# untitled.net
KiCad netlist of a schematic drawn in EAGLE
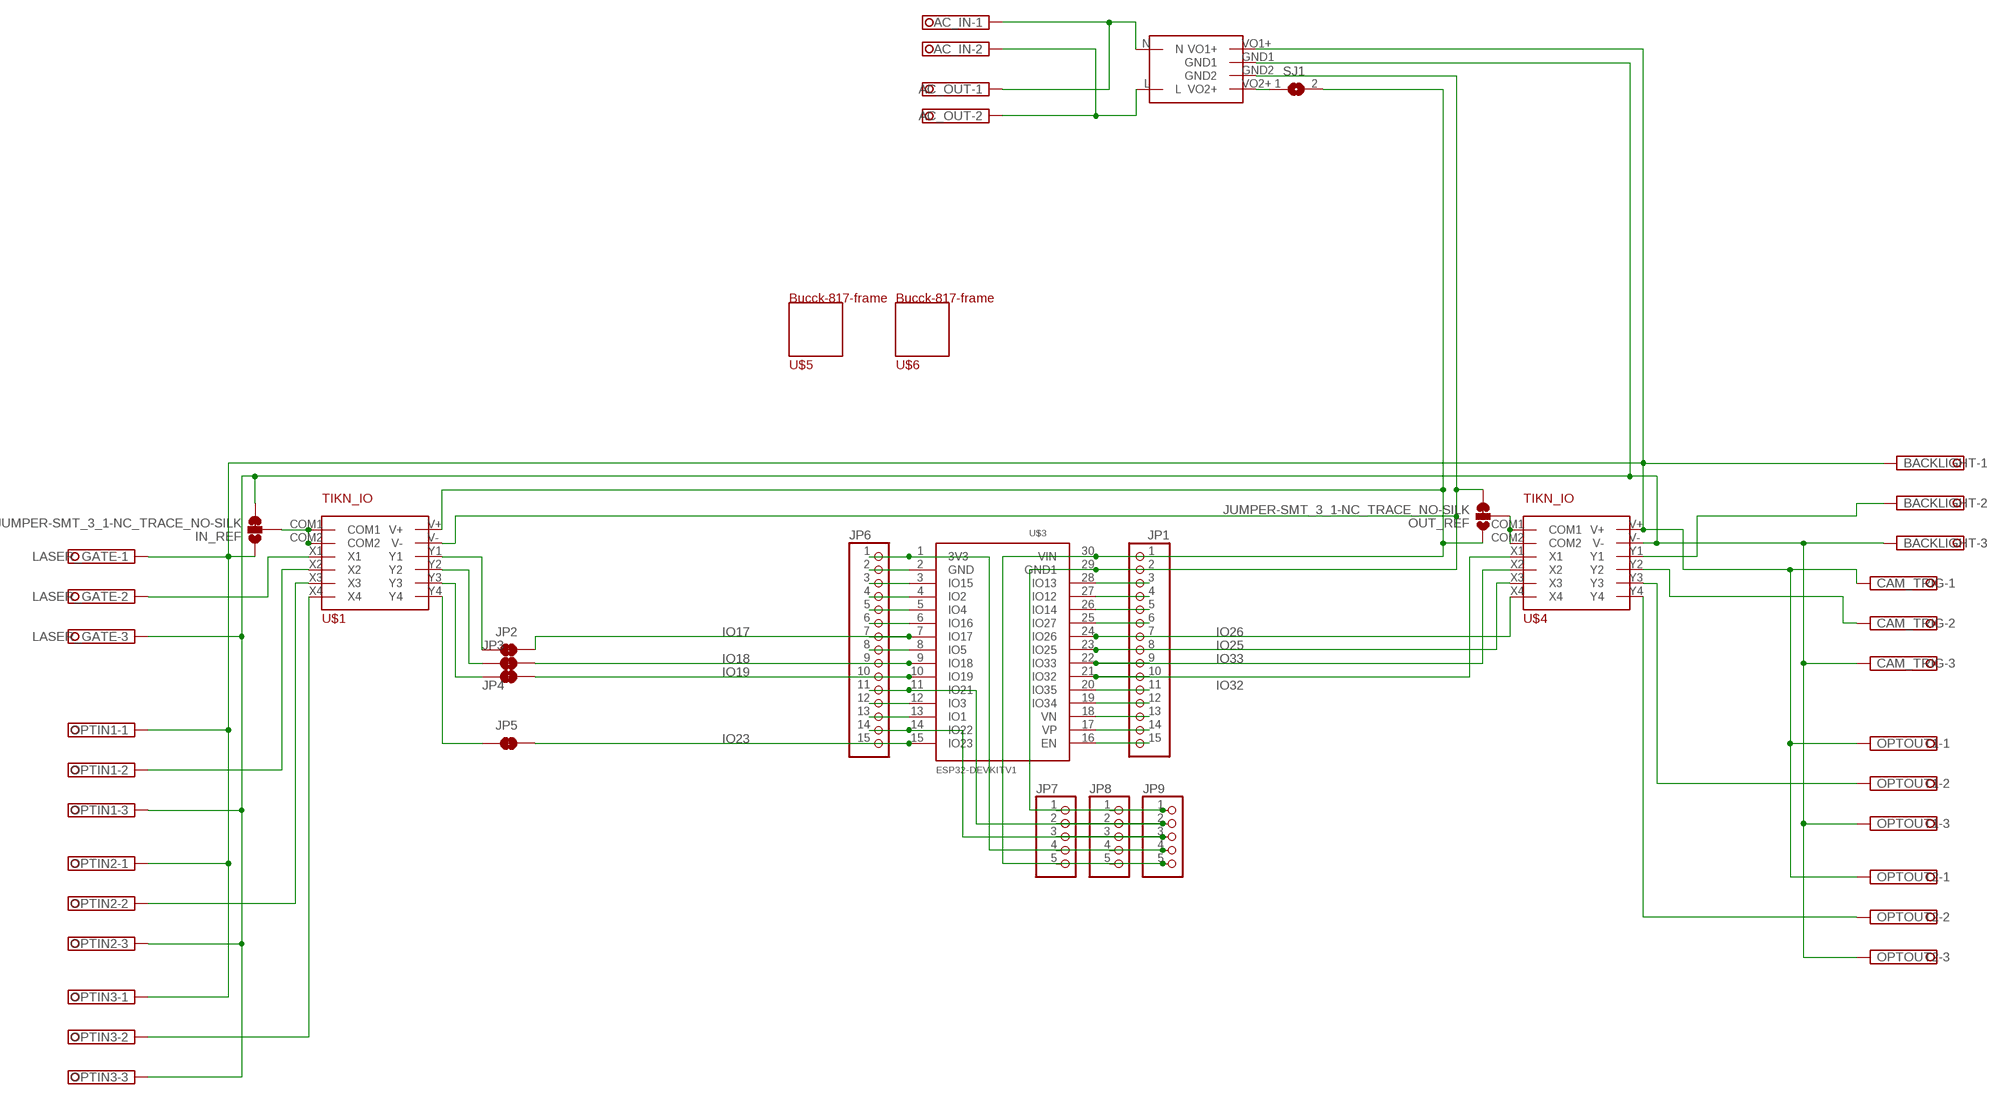
[diagram p0: schematic, sheet 1]

(export (version "E")
  (design (tool "Eeschema 10.0.6"))
  (components
    (comp (ref "AC_IN")
      (value "TERMINAL-BLOCK-3.5MM-2-PIN-LONG-PAD")
      (footprint "eagle-import:TERMINAL-BLOCK-2-PIN-3.5MM-LONG-PAD")
      (libsource (lib "eagle-import") (part "TERMINAL-BLOCK-3.5MM-2-PIN-LONG-PAD"))
    )
    (comp (ref "AC_OUT")
      (value "TERMINAL-BLOCK-3.5MM-2-PIN-LONG-PAD")
      (footprint "eagle-import:TERMINAL-BLOCK-2-PIN-3.5MM-LONG-PAD")
      (libsource (lib "eagle-import") (part "TERMINAL-BLOCK-3.5MM-2-PIN-LONG-PAD"))
    )
    (comp (ref "BACKLIGHT")
      (value "TERMINAL-BLOCK-3.5MM-3-PIN-LONG-PAD")
      (footprint "eagle-import:TERMINAL-BLOCK-3-PIN-3.5MM-LONG-PAD")
      (libsource (lib "eagle-import") (part "TERMINAL-BLOCK-3.5MM-3-PIN-LONG-PAD"))
    )
    (comp (ref "CAM_TRIG")
      (value "TERMINAL-BLOCK-3.5MM-3-PIN-LONG-PAD")
      (footprint "eagle-import:TERMINAL-BLOCK-3-PIN-3.5MM-LONG-PAD")
      (libsource (lib "eagle-import") (part "TERMINAL-BLOCK-3.5MM-3-PIN-LONG-PAD"))
    )
    (comp (ref "IN_REF")
      (value "JUMPER-SMT_3_1-NC_TRACE_NO-SILK")
      (footprint "eagle-import:SMT-JUMPER_3_1-NC_TRACE_NO-SILK")
      (libsource (lib "eagle-import") (part "JUMPER-SMT_3_1-NC_TRACE_NO-SILK"))
    )
    (comp (ref "JP1")
      (value "PINHD-1X15")
      (footprint "eagle-import:1X15")
      (libsource (lib "eagle-import") (part "PINHD-1X15"))
    )
    (comp (ref "JP2")
      (value "JUMPER-SMT_2_NC_TRACE_SILK")
      (footprint "eagle-import:SMT-JUMPER_2_NC_TRACE_SILK")
      (libsource (lib "eagle-import") (part "JUMPER-SMT_2_NC_TRACE_SILK"))
    )
    (comp (ref "JP3")
      (value "JUMPER-SMT_2_NC_TRACE_SILK")
      (footprint "eagle-import:SMT-JUMPER_2_NC_TRACE_SILK")
      (libsource (lib "eagle-import") (part "JUMPER-SMT_2_NC_TRACE_SILK"))
    )
    (comp (ref "JP4")
      (value "JUMPER-SMT_2_NC_TRACE_SILK")
      (footprint "eagle-import:SMT-JUMPER_2_NC_TRACE_SILK")
      (libsource (lib "eagle-import") (part "JUMPER-SMT_2_NC_TRACE_SILK"))
    )
    (comp (ref "JP5")
      (value "JUMPER-SMT_2_NC_TRACE_SILK")
      (footprint "eagle-import:SMT-JUMPER_2_NC_TRACE_SILK")
      (libsource (lib "eagle-import") (part "JUMPER-SMT_2_NC_TRACE_SILK"))
    )
    (comp (ref "JP6")
      (value "PINHD-1X15")
      (footprint "eagle-import:1X15")
      (libsource (lib "eagle-import") (part "PINHD-1X15"))
    )
    (comp (ref "JP7")
      (value "PINHD-1X5")
      (footprint "eagle-import:1X05")
      (libsource (lib "eagle-import") (part "PINHD-1X5"))
    )
    (comp (ref "JP8")
      (value "PINHD-1X5")
      (footprint "eagle-import:1X05")
      (libsource (lib "eagle-import") (part "PINHD-1X5"))
    )
    (comp (ref "JP9")
      (value "PINHD-1X5")
      (footprint "eagle-import:1X05")
      (libsource (lib "eagle-import") (part "PINHD-1X5"))
    )
    (comp (ref "LASER_GATE")
      (value "TERMINAL-BLOCK-3.5MM-3-PIN-LONG-PAD")
      (footprint "eagle-import:TERMINAL-BLOCK-3-PIN-3.5MM-LONG-PAD")
      (libsource (lib "eagle-import") (part "TERMINAL-BLOCK-3.5MM-3-PIN-LONG-PAD"))
    )
    (comp (ref "OPTIN1")
      (value "TERMINAL-BLOCK-3.5MM-3-PIN-LONG-PAD")
      (footprint "eagle-import:TERMINAL-BLOCK-3-PIN-3.5MM-LONG-PAD")
      (libsource (lib "eagle-import") (part "TERMINAL-BLOCK-3.5MM-3-PIN-LONG-PAD"))
    )
    (comp (ref "OPTIN2")
      (value "TERMINAL-BLOCK-3.5MM-3-PIN-LONG-PAD")
      (footprint "eagle-import:TERMINAL-BLOCK-3-PIN-3.5MM-LONG-PAD")
      (libsource (lib "eagle-import") (part "TERMINAL-BLOCK-3.5MM-3-PIN-LONG-PAD"))
    )
    (comp (ref "OPTIN3")
      (value "TERMINAL-BLOCK-3.5MM-3-PIN-LONG-PAD")
      (footprint "eagle-import:TERMINAL-BLOCK-3-PIN-3.5MM-LONG-PAD")
      (libsource (lib "eagle-import") (part "TERMINAL-BLOCK-3.5MM-3-PIN-LONG-PAD"))
    )
    (comp (ref "OPTOUT1")
      (value "TERMINAL-BLOCK-3.5MM-3-PIN-LONG-PAD")
      (footprint "eagle-import:TERMINAL-BLOCK-3-PIN-3.5MM-LONG-PAD")
      (libsource (lib "eagle-import") (part "TERMINAL-BLOCK-3.5MM-3-PIN-LONG-PAD"))
    )
    (comp (ref "OPTOUT2")
      (value "TERMINAL-BLOCK-3.5MM-3-PIN-LONG-PAD")
      (footprint "eagle-import:TERMINAL-BLOCK-3-PIN-3.5MM-LONG-PAD")
      (libsource (lib "eagle-import") (part "TERMINAL-BLOCK-3.5MM-3-PIN-LONG-PAD"))
    )
    (comp (ref "OUT_REF")
      (value "JUMPER-SMT_3_1-NC_TRACE_NO-SILK")
      (footprint "eagle-import:SMT-JUMPER_3_1-NC_TRACE_NO-SILK")
      (libsource (lib "eagle-import") (part "JUMPER-SMT_3_1-NC_TRACE_NO-SILK"))
    )
    (comp (ref "SJ1")
      (value "SJW")
      (footprint "eagle-import:SJW")
      (libsource (lib "eagle-import") (part "SJW"))
    )
    (comp (ref "U$1")
      (value "TIKN_IO_ISOLATOR2")
      (footprint "eagle-import:IO_ISOLATOR2")
      (libsource (lib "eagle-import") (part "TIKN_IO_ISOLATOR2"))
    )
    (comp (ref "U$2")
      (value "AM22-24W1205V")
      (footprint "eagle-import:AM22-24W1205V")
      (libsource (lib "eagle-import") (part "AM22-24W1205V"))
    )
    (comp (ref "U$3")
      (value "ESP32DEVKITV1")
      (footprint "eagle-import:ESP32-DEVKITV1")
      (libsource (lib "eagle-import") (part "ESP32DEVKITV1"))
    )
    (comp (ref "U$4")
      (value "TIKN_IO_ISOLATOR2")
      (footprint "eagle-import:IO_ISOLATOR2")
      (libsource (lib "eagle-import") (part "TIKN_IO_ISOLATOR2"))
    )
    (comp (ref "U$5")
      (value "BUCC-817")
      (footprint "eagle-import:BUCCK-817")
      (libsource (lib "eagle-import") (part "BUCC-817"))
    )
    (comp (ref "U$6")
      (value "BUCC-817")
      (footprint "eagle-import:BUCCK-817")
      (libsource (lib "eagle-import") (part "BUCC-817"))
    )
  )
  (nets
    (net (code "1") (name "/IO17") (class "Default")
      (node (ref "JP2") (pin "2") (pinfunction "2_2") (pintype "passive"))
      (node (ref "JP6") (pin "7") (pinfunction "7_7") (pintype "passive"))
      (node (ref "U$3") (pin "7") (pinfunction "IO17_7") (pintype "bidirectional"))
    )
    (net (code "2") (name "/IO18") (class "Default")
      (node (ref "JP3") (pin "2") (pinfunction "2_2") (pintype "passive"))
      (node (ref "JP6") (pin "9") (pinfunction "9_9") (pintype "passive"))
      (node (ref "U$3") (pin "9") (pinfunction "IO18_9") (pintype "bidirectional"))
    )
    (net (code "3") (name "/IO19") (class "Default")
      (node (ref "JP4") (pin "2") (pinfunction "2_2") (pintype "passive"))
      (node (ref "JP6") (pin "10") (pinfunction "10_10") (pintype "passive"))
      (node (ref "U$3") (pin "10") (pinfunction "IO19_10") (pintype "bidirectional"))
    )
    (net (code "4") (name "/IO23") (class "Default")
      (node (ref "JP5") (pin "2") (pinfunction "2_2") (pintype "passive"))
      (node (ref "JP6") (pin "15") (pinfunction "15_15") (pintype "passive"))
      (node (ref "U$3") (pin "15") (pinfunction "IO23_15") (pintype "bidirectional"))
    )
    (net (code "5") (name "/IO25") (class "Default")
      (node (ref "JP1") (pin "8") (pinfunction "8_8") (pintype "passive"))
      (node (ref "U$3") (pin "23") (pinfunction "IO25_23") (pintype "bidirectional"))
      (node (ref "U$4") (pin "X3") (pinfunction "X3_X3") (pintype "bidirectional"))
    )
    (net (code "6") (name "/IO26") (class "Default")
      (node (ref "JP1") (pin "7") (pinfunction "7_7") (pintype "passive"))
      (node (ref "U$3") (pin "24") (pinfunction "IO26_24") (pintype "bidirectional"))
      (node (ref "U$4") (pin "X4") (pinfunction "X4_X4") (pintype "bidirectional"))
    )
    (net (code "7") (name "/IO32") (class "Default")
      (node (ref "JP1") (pin "10") (pinfunction "10_10") (pintype "passive"))
      (node (ref "U$3") (pin "21") (pinfunction "IO32_21") (pintype "bidirectional"))
      (node (ref "U$4") (pin "X1") (pinfunction "X1_X1") (pintype "bidirectional"))
    )
    (net (code "8") (name "/IO33") (class "Default")
      (node (ref "JP1") (pin "9") (pinfunction "9_9") (pintype "passive"))
      (node (ref "U$3") (pin "22") (pinfunction "IO33_22") (pintype "bidirectional"))
      (node (ref "U$4") (pin "X2") (pinfunction "X2_X2") (pintype "bidirectional"))
    )
    (net (code "9") (name "Net-(AC_INA-K)") (class "Default")
      (node (ref "AC_IN") (pin "1") (pinfunction "K_1") (pintype "passive"))
      (node (ref "AC_OUT") (pin "1") (pinfunction "K_1") (pintype "passive"))
      (node (ref "U$2") (pin "N") (pinfunction "N_N") (pintype "bidirectional"))
    )
    (net (code "10") (name "Net-(AC_INB-K)") (class "Default")
      (node (ref "AC_IN") (pin "2") (pinfunction "K_2") (pintype "passive"))
      (node (ref "AC_OUT") (pin "2") (pinfunction "K_2") (pintype "passive"))
      (node (ref "U$2") (pin "L") (pinfunction "L_L") (pintype "bidirectional"))
    )
    (net (code "11") (name "Net-(BACKLIGHTA-K)") (class "Default")
      (node (ref "BACKLIGHT") (pin "1") (pinfunction "K_1") (pintype "passive"))
      (node (ref "CAM_TRIG") (pin "1") (pinfunction "K_1") (pintype "passive"))
      (node (ref "IN_REF") (pin "1") (pinfunction "1_1") (pintype "passive"))
      (node (ref "LASER_GATE") (pin "1") (pinfunction "K_1") (pintype "passive"))
      (node (ref "OPTIN1") (pin "1") (pinfunction "K_1") (pintype "passive"))
      (node (ref "OPTIN2") (pin "1") (pinfunction "K_1") (pintype "passive"))
      (node (ref "OPTIN3") (pin "1") (pinfunction "K_1") (pintype "passive"))
      (node (ref "OPTOUT1") (pin "1") (pinfunction "K_1") (pintype "passive"))
      (node (ref "OPTOUT2") (pin "1") (pinfunction "K_1") (pintype "passive"))
      (node (ref "U$2") (pin "VO1+") (pinfunction "VO1+_VO1+") (pintype "bidirectional"))
      (node (ref "U$4") (pin "V+") (pinfunction "V+_V+") (pintype "bidirectional"))
    )
    (net (code "12") (name "Net-(BACKLIGHTB-K)") (class "Default")
      (node (ref "BACKLIGHT") (pin "2") (pinfunction "K_2") (pintype "passive"))
      (node (ref "U$4") (pin "Y1") (pinfunction "Y1_Y1") (pintype "bidirectional"))
    )
    (net (code "13") (name "Net-(BACKLIGHTC-K)") (class "Default")
      (node (ref "BACKLIGHT") (pin "3") (pinfunction "K_3") (pintype "passive"))
      (node (ref "CAM_TRIG") (pin "3") (pinfunction "K_3") (pintype "passive"))
      (node (ref "IN_REF") (pin "3") (pinfunction "3_3") (pintype "passive"))
      (node (ref "LASER_GATE") (pin "3") (pinfunction "K_3") (pintype "passive"))
      (node (ref "OPTIN1") (pin "3") (pinfunction "K_3") (pintype "passive"))
      (node (ref "OPTIN2") (pin "3") (pinfunction "K_3") (pintype "passive"))
      (node (ref "OPTIN3") (pin "3") (pinfunction "K_3") (pintype "passive"))
      (node (ref "OPTOUT1") (pin "3") (pinfunction "K_3") (pintype "passive"))
      (node (ref "OPTOUT2") (pin "3") (pinfunction "K_3") (pintype "passive"))
      (node (ref "U$2") (pin "GND1") (pinfunction "GND1_GND1") (pintype "bidirectional"))
      (node (ref "U$4") (pin "V-") (pinfunction "V-_V-") (pintype "bidirectional"))
    )
    (net (code "14") (name "Net-(CAM_TRIGB-K)") (class "Default")
      (node (ref "CAM_TRIG") (pin "2") (pinfunction "K_2") (pintype "passive"))
      (node (ref "U$4") (pin "Y2") (pinfunction "Y2_Y2") (pintype "bidirectional"))
    )
    (net (code "15") (name "Net-(IN_REF-Pad2)") (class "Default")
      (node (ref "IN_REF") (pin "2") (pinfunction "2_2") (pintype "passive"))
      (node (ref "U$1") (pin "COM1") (pinfunction "COM1_COM1") (pintype "bidirectional"))
      (node (ref "U$1") (pin "COM2") (pinfunction "COM2_COM2") (pintype "bidirectional"))
    )
    (net (code "16") (name "Net-(JP2-Pad1)") (class "Default")
      (node (ref "JP2") (pin "1") (pinfunction "1_1") (pintype "passive"))
      (node (ref "U$1") (pin "Y1") (pinfunction "Y1_Y1") (pintype "bidirectional"))
    )
    (net (code "17") (name "Net-(JP3-Pad1)") (class "Default")
      (node (ref "JP3") (pin "1") (pinfunction "1_1") (pintype "passive"))
      (node (ref "U$1") (pin "Y2") (pinfunction "Y2_Y2") (pintype "bidirectional"))
    )
    (net (code "18") (name "Net-(JP4-Pad1)") (class "Default")
      (node (ref "JP4") (pin "1") (pinfunction "1_1") (pintype "passive"))
      (node (ref "U$1") (pin "Y3") (pinfunction "Y3_Y3") (pintype "bidirectional"))
    )
    (net (code "19") (name "Net-(JP5-Pad1)") (class "Default")
      (node (ref "JP5") (pin "1") (pinfunction "1_1") (pintype "passive"))
      (node (ref "U$1") (pin "Y4") (pinfunction "Y4_Y4") (pintype "bidirectional"))
    )
    (net (code "20") (name "Net-(LASER_GATEB-K)") (class "Default")
      (node (ref "LASER_GATE") (pin "2") (pinfunction "K_2") (pintype "passive"))
      (node (ref "U$1") (pin "X1") (pinfunction "X1_X1") (pintype "bidirectional"))
    )
    (net (code "21") (name "Net-(OPTIN1B-K)") (class "Default")
      (node (ref "OPTIN1") (pin "2") (pinfunction "K_2") (pintype "passive"))
      (node (ref "U$1") (pin "X2") (pinfunction "X2_X2") (pintype "bidirectional"))
    )
    (net (code "22") (name "Net-(OPTIN2B-K)") (class "Default")
      (node (ref "OPTIN2") (pin "2") (pinfunction "K_2") (pintype "passive"))
      (node (ref "U$1") (pin "X3") (pinfunction "X3_X3") (pintype "bidirectional"))
    )
    (net (code "23") (name "Net-(OPTIN3B-K)") (class "Default")
      (node (ref "OPTIN3") (pin "2") (pinfunction "K_2") (pintype "passive"))
      (node (ref "U$1") (pin "X4") (pinfunction "X4_X4") (pintype "bidirectional"))
    )
    (net (code "24") (name "Net-(OPTOUT1B-K)") (class "Default")
      (node (ref "OPTOUT1") (pin "2") (pinfunction "K_2") (pintype "passive"))
      (node (ref "U$4") (pin "Y3") (pinfunction "Y3_Y3") (pintype "bidirectional"))
    )
    (net (code "25") (name "Net-(OPTOUT2B-K)") (class "Default")
      (node (ref "OPTOUT2") (pin "2") (pinfunction "K_2") (pintype "passive"))
      (node (ref "U$4") (pin "Y4") (pinfunction "Y4_Y4") (pintype "bidirectional"))
    )
    (net (code "26") (name "Net-(OUT_REF-Pad2)") (class "Default")
      (node (ref "OUT_REF") (pin "2") (pinfunction "2_2") (pintype "passive"))
      (node (ref "U$4") (pin "COM1") (pinfunction "COM1_COM1") (pintype "bidirectional"))
      (node (ref "U$4") (pin "COM2") (pinfunction "COM2_COM2") (pintype "bidirectional"))
    )
    (net (code "27") (name "Net-(SJ1-Pad1)") (class "Default")
      (node (ref "SJ1") (pin "1") (pinfunction "1_1") (pintype "passive"))
      (node (ref "U$2") (pin "VO2+") (pinfunction "VO2+_VO2+") (pintype "bidirectional"))
    )
    (net (code "28") (name "Net-(U$3-3V3)") (class "Default")
      (node (ref "JP6") (pin "1") (pinfunction "1_1") (pintype "passive"))
      (node (ref "JP7") (pin "4") (pinfunction "4_4") (pintype "passive"))
      (node (ref "JP8") (pin "4") (pinfunction "4_4") (pintype "passive"))
      (node (ref "JP9") (pin "4") (pinfunction "4_4") (pintype "passive"))
      (node (ref "U$3") (pin "1") (pinfunction "3V3_1") (pintype "bidirectional"))
    )
    (net (code "29") (name "Net-(U$3-EN)") (class "Default")
      (node (ref "JP1") (pin "15") (pinfunction "15_15") (pintype "passive"))
      (node (ref "U$3") (pin "16") (pinfunction "EN_16") (pintype "bidirectional"))
    )
    (net (code "30") (name "Net-(U$3-GND)") (class "Default")
      (node (ref "JP6") (pin "2") (pinfunction "2_2") (pintype "passive"))
      (node (ref "U$3") (pin "2") (pinfunction "GND_2") (pintype "bidirectional"))
    )
    (net (code "31") (name "Net-(U$3-GND1)") (class "Default")
      (node (ref "JP1") (pin "2") (pinfunction "2_2") (pintype "passive"))
      (node (ref "JP7") (pin "1") (pinfunction "1_1") (pintype "passive"))
      (node (ref "JP8") (pin "1") (pinfunction "1_1") (pintype "passive"))
      (node (ref "JP9") (pin "1") (pinfunction "1_1") (pintype "passive"))
      (node (ref "OUT_REF") (pin "3") (pinfunction "3_3") (pintype "passive"))
      (node (ref "U$1") (pin "V-") (pinfunction "V-_V-") (pintype "bidirectional"))
      (node (ref "U$2") (pin "GND2") (pinfunction "GND2_GND2") (pintype "bidirectional"))
      (node (ref "U$3") (pin "29") (pinfunction "GND1_29") (pintype "bidirectional"))
    )
    (net (code "32") (name "Net-(U$3-IO1)") (class "Default")
      (node (ref "JP6") (pin "13") (pinfunction "13_13") (pintype "passive"))
      (node (ref "U$3") (pin "13") (pinfunction "IO1_13") (pintype "bidirectional"))
    )
    (net (code "33") (name "Net-(U$3-IO2)") (class "Default")
      (node (ref "JP6") (pin "4") (pinfunction "4_4") (pintype "passive"))
      (node (ref "U$3") (pin "4") (pinfunction "IO2_4") (pintype "bidirectional"))
    )
    (net (code "34") (name "Net-(U$3-IO3)") (class "Default")
      (node (ref "JP6") (pin "12") (pinfunction "12_12") (pintype "passive"))
      (node (ref "U$3") (pin "12") (pinfunction "IO3_12") (pintype "bidirectional"))
    )
    (net (code "35") (name "Net-(U$3-IO4)") (class "Default")
      (node (ref "JP6") (pin "5") (pinfunction "5_5") (pintype "passive"))
      (node (ref "U$3") (pin "5") (pinfunction "IO4_5") (pintype "bidirectional"))
    )
    (net (code "36") (name "Net-(U$3-IO5)") (class "Default")
      (node (ref "JP6") (pin "8") (pinfunction "8_8") (pintype "passive"))
      (node (ref "U$3") (pin "8") (pinfunction "IO5_8") (pintype "bidirectional"))
    )
    (net (code "37") (name "Net-(U$3-IO12)") (class "Default")
      (node (ref "JP1") (pin "4") (pinfunction "4_4") (pintype "passive"))
      (node (ref "U$3") (pin "27") (pinfunction "IO12_27") (pintype "bidirectional"))
    )
    (net (code "38") (name "Net-(U$3-IO13)") (class "Default")
      (node (ref "JP1") (pin "3") (pinfunction "3_3") (pintype "passive"))
      (node (ref "U$3") (pin "28") (pinfunction "IO13_28") (pintype "bidirectional"))
    )
    (net (code "39") (name "Net-(U$3-IO14)") (class "Default")
      (node (ref "JP1") (pin "5") (pinfunction "5_5") (pintype "passive"))
      (node (ref "U$3") (pin "26") (pinfunction "IO14_26") (pintype "bidirectional"))
    )
    (net (code "40") (name "Net-(U$3-IO15)") (class "Default")
      (node (ref "JP6") (pin "3") (pinfunction "3_3") (pintype "passive"))
      (node (ref "U$3") (pin "3") (pinfunction "IO15_3") (pintype "bidirectional"))
    )
    (net (code "41") (name "Net-(U$3-IO16)") (class "Default")
      (node (ref "JP6") (pin "6") (pinfunction "6_6") (pintype "passive"))
      (node (ref "U$3") (pin "6") (pinfunction "IO16_6") (pintype "bidirectional"))
    )
    (net (code "42") (name "Net-(U$3-IO21)") (class "Default")
      (node (ref "JP6") (pin "11") (pinfunction "11_11") (pintype "passive"))
      (node (ref "JP7") (pin "2") (pinfunction "2_2") (pintype "passive"))
      (node (ref "JP8") (pin "2") (pinfunction "2_2") (pintype "passive"))
      (node (ref "JP9") (pin "2") (pinfunction "2_2") (pintype "passive"))
      (node (ref "U$3") (pin "11") (pinfunction "IO21_11") (pintype "bidirectional"))
    )
    (net (code "43") (name "Net-(U$3-IO22)") (class "Default")
      (node (ref "JP6") (pin "14") (pinfunction "14_14") (pintype "passive"))
      (node (ref "JP7") (pin "3") (pinfunction "3_3") (pintype "passive"))
      (node (ref "JP8") (pin "3") (pinfunction "3_3") (pintype "passive"))
      (node (ref "JP9") (pin "3") (pinfunction "3_3") (pintype "passive"))
      (node (ref "U$3") (pin "14") (pinfunction "IO22_14") (pintype "bidirectional"))
    )
    (net (code "44") (name "Net-(U$3-IO27)") (class "Default")
      (node (ref "JP1") (pin "6") (pinfunction "6_6") (pintype "passive"))
      (node (ref "U$3") (pin "25") (pinfunction "IO27_25") (pintype "bidirectional"))
    )
    (net (code "45") (name "Net-(U$3-IO34)") (class "Default")
      (node (ref "JP1") (pin "12") (pinfunction "12_12") (pintype "passive"))
      (node (ref "U$3") (pin "19") (pinfunction "IO34_19") (pintype "bidirectional"))
    )
    (net (code "46") (name "Net-(U$3-IO35)") (class "Default")
      (node (ref "JP1") (pin "11") (pinfunction "11_11") (pintype "passive"))
      (node (ref "U$3") (pin "20") (pinfunction "IO35_20") (pintype "bidirectional"))
    )
    (net (code "47") (name "Net-(U$3-VIN)") (class "Default")
      (node (ref "JP1") (pin "1") (pinfunction "1_1") (pintype "passive"))
      (node (ref "JP7") (pin "5") (pinfunction "5_5") (pintype "passive"))
      (node (ref "JP8") (pin "5") (pinfunction "5_5") (pintype "passive"))
      (node (ref "JP9") (pin "5") (pinfunction "5_5") (pintype "passive"))
      (node (ref "OUT_REF") (pin "1") (pinfunction "1_1") (pintype "passive"))
      (node (ref "SJ1") (pin "2") (pinfunction "2_2") (pintype "passive"))
      (node (ref "U$1") (pin "V+") (pinfunction "V+_V+") (pintype "bidirectional"))
      (node (ref "U$3") (pin "30") (pinfunction "VIN_30") (pintype "bidirectional"))
    )
    (net (code "48") (name "Net-(U$3-VN)") (class "Default")
      (node (ref "JP1") (pin "13") (pinfunction "13_13") (pintype "passive"))
      (node (ref "U$3") (pin "18") (pinfunction "VN_18") (pintype "bidirectional"))
    )
    (net (code "49") (name "Net-(U$3-VP)") (class "Default")
      (node (ref "JP1") (pin "14") (pinfunction "14_14") (pintype "passive"))
      (node (ref "U$3") (pin "17") (pinfunction "VP_17") (pintype "bidirectional"))
    )
  )
)
